# schematic.net
KiCad netlist of a schematic drawn in Altium Designer
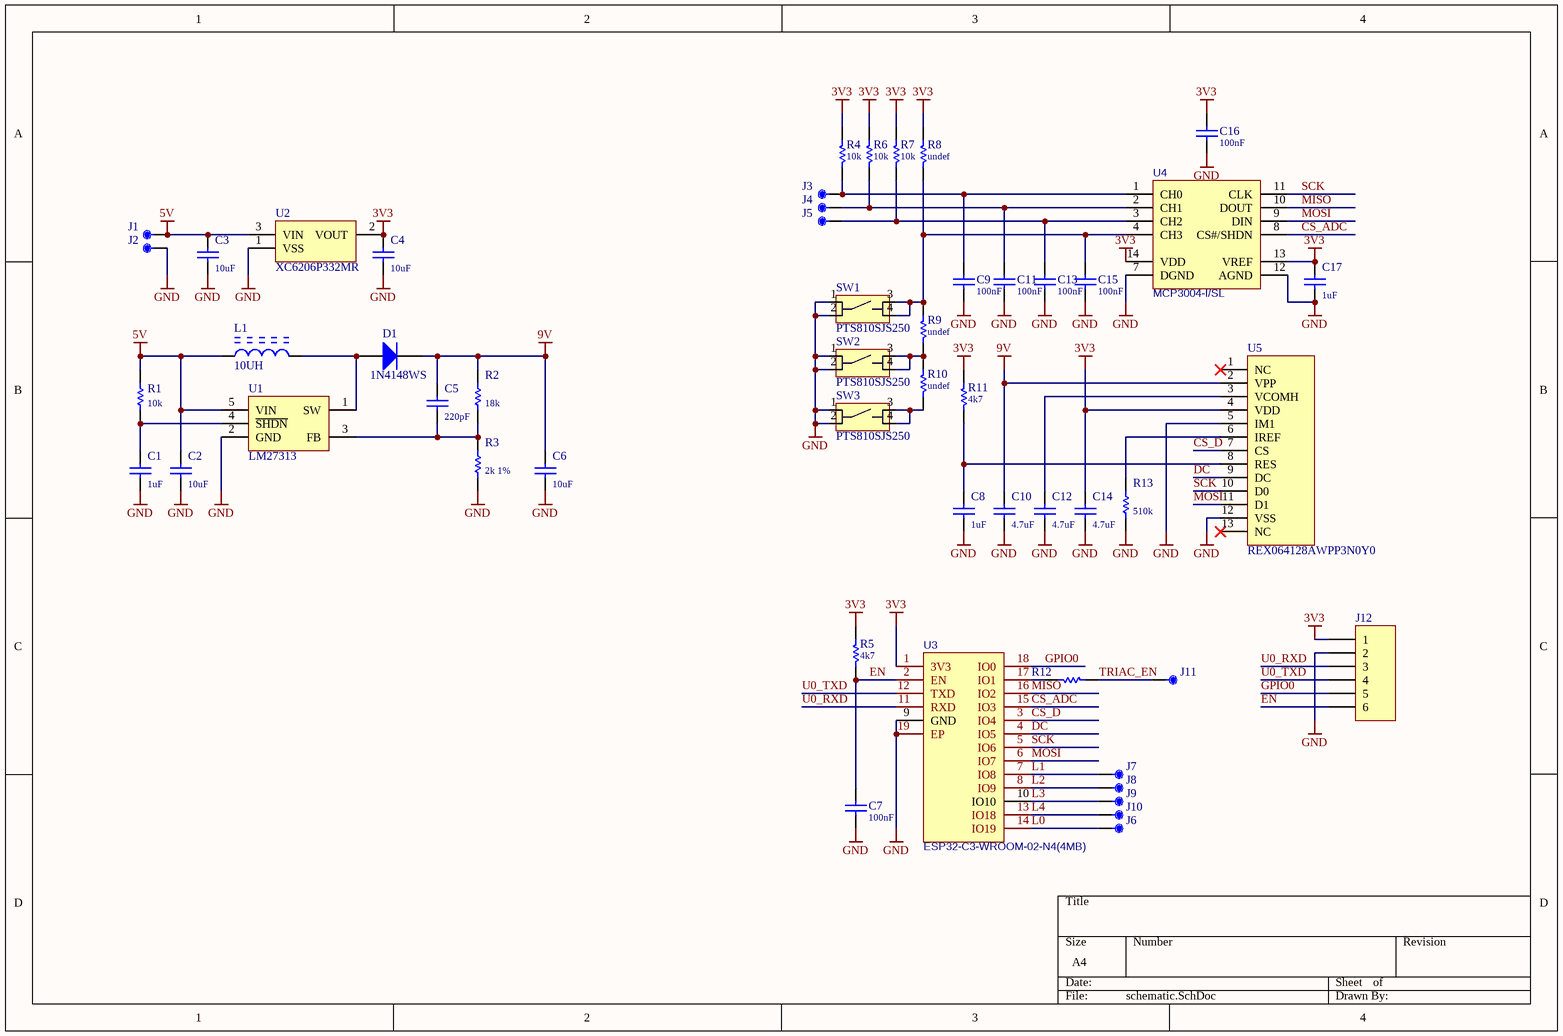
[diagram p0: schematic.SchDoc]

(export (version "E")
  (design (tool "Eeschema 10.0.6"))
  (components
    (comp (ref "C1")
      (value "1uF")
      (footprint "C0603")
      (description "1uF 0603")
      (libsource (lib "Miscellaneous Devices") (part "CAP"))
    )
    (comp (ref "C2")
      (value "10uF")
      (footprint "C1206")
      (description "10uf 25V 1206")
      (libsource (lib "Miscellaneous Devices") (part "CAP"))
    )
    (comp (ref "C3")
      (value "10uF")
      (footprint "C1206")
      (description "10uf 50V 1206")
      (libsource (lib "Miscellaneous Devices") (part "CAP"))
    )
    (comp (ref "C4")
      (value "10uF")
      (footprint "C1206")
      (description "10uf 50V 1206")
      (libsource (lib "Miscellaneous Devices") (part "CAP"))
    )
    (comp (ref "C5")
      (value "220pF")
      (footprint "C0402")
      (description "220pF 0402")
      (libsource (lib "Miscellaneous Devices") (part "CAP"))
    )
    (comp (ref "C6")
      (value "10uF")
      (footprint "C1206")
      (description "10uf 25V 1206")
      (libsource (lib "Miscellaneous Devices") (part "CAP"))
    )
    (comp (ref "C7")
      (value "100nF")
      (footprint "C0402")
      (description "100nF 0402")
      (libsource (lib "Miscellaneous Devices") (part "CAP"))
    )
    (comp (ref "C8")
      (value "1uF")
      (footprint "C0603")
      (description "1uF 0603")
      (libsource (lib "Miscellaneous Devices") (part "CAP"))
    )
    (comp (ref "C9")
      (value "100nF")
      (footprint "C0402")
      (description "100nF 0402")
      (libsource (lib "Miscellaneous Devices") (part "CAP"))
    )
    (comp (ref "C10")
      (value "4.7uF")
      (footprint "C0805")
      (description "4.7uF 50V 0805")
      (libsource (lib "Miscellaneous Devices") (part "CAP"))
    )
    (comp (ref "C11")
      (value "100nF")
      (footprint "C0402")
      (description "100nF 0402")
      (libsource (lib "Miscellaneous Devices") (part "CAP"))
    )
    (comp (ref "C12")
      (value "4.7uF")
      (footprint "C0805")
      (description "4.7uF 50V 0805")
      (libsource (lib "Miscellaneous Devices") (part "CAP"))
    )
    (comp (ref "C13")
      (value "100nF")
      (footprint "C0402")
      (description "100nF 0402")
      (libsource (lib "Miscellaneous Devices") (part "CAP"))
    )
    (comp (ref "C14")
      (value "4.7uF")
      (footprint "C0805")
      (description "4.7uF 50V 0805")
      (libsource (lib "Miscellaneous Devices") (part "CAP"))
    )
    (comp (ref "C15")
      (value "100nF")
      (footprint "C0402")
      (description "100nF 0402")
      (libsource (lib "Miscellaneous Devices") (part "CAP"))
    )
    (comp (ref "C16")
      (value "100nF")
      (footprint "C0402")
      (description "100nF 0402")
      (libsource (lib "Miscellaneous Devices") (part "CAP"))
    )
    (comp (ref "C17")
      (value "1uF")
      (footprint "C0603")
      (description "1uF 0603")
      (libsource (lib "Miscellaneous Devices") (part "CAP"))
    )
    (comp (ref "D1")
      (value "1N4148WS")
      (footprint "SOD-323")
      (libsource (lib "Miscellaneous Devices") (part "US1M-13-F"))
    )
    (comp (ref "J1")
      (value "undef")
      (footprint "TP30_SMD")
      (libsource (lib "Miscellaneous Connectors") (part "TP_Dup1"))
    )
    (comp (ref "J2")
      (value "undef")
      (footprint "TP30_SMD")
      (libsource (lib "Miscellaneous Connectors") (part "TP_Dup1"))
    )
    (comp (ref "J3")
      (value "undef")
      (footprint "TP30_SMD")
      (libsource (lib "Miscellaneous Connectors") (part "TP_Dup1"))
    )
    (comp (ref "J4")
      (value "undef")
      (footprint "TP30_SMD")
      (libsource (lib "Miscellaneous Connectors") (part "TP_Dup1"))
    )
    (comp (ref "J5")
      (value "undef")
      (footprint "TP30_SMD")
      (libsource (lib "Miscellaneous Connectors") (part "TP_Dup1"))
    )
    (comp (ref "J6")
      (value "undef")
      (footprint "TP30_SMD")
      (libsource (lib "Miscellaneous Connectors") (part "TP_Dup1"))
    )
    (comp (ref "J7")
      (value "undef")
      (footprint "TP30_SMD")
      (libsource (lib "Miscellaneous Connectors") (part "TP_Dup1"))
    )
    (comp (ref "J8")
      (value "undef")
      (footprint "TP30_SMD")
      (libsource (lib "Miscellaneous Connectors") (part "TP_Dup1"))
    )
    (comp (ref "J9")
      (value "undef")
      (footprint "TP30_SMD")
      (libsource (lib "Miscellaneous Connectors") (part "TP_Dup1"))
    )
    (comp (ref "J10")
      (value "undef")
      (footprint "TP30_SMD")
      (libsource (lib "Miscellaneous Connectors") (part "TP_Dup1"))
    )
    (comp (ref "J11")
      (value "undef")
      (footprint "TP30_SMD")
      (libsource (lib "Miscellaneous Connectors") (part "TP_Dup1"))
    )
    (comp (ref "J12") (value "~") (footprint "HDR-1X6") (libsource (lib "Schlib1") (part "Header 3_1")))
    (comp (ref "L1")
      (value "10UH")
      (footprint "L2520")
      (description "VLS252012HBX-100M-1")
      (libsource (lib "Miscellaneous Devices") (part "SRN3015-100M"))
    )
    (comp (ref "R1")
      (value "10k")
      (footprint "R0402")
      (description "10k 0402")
      (libsource (lib "Miscellaneous Devices") (part "RES"))
    )
    (comp (ref "R2")
      (value "18k")
      (footprint "R0402")
      (description "18k 0402")
      (libsource (lib "Miscellaneous Devices") (part "RES"))
    )
    (comp (ref "R3")
      (value "2k 1%")
      (footprint "R0402")
      (description "2k 0402")
      (libsource (lib "Miscellaneous Devices") (part "RES"))
    )
    (comp (ref "R4")
      (value "10k")
      (footprint "R0603")
      (description "10k 0603")
      (libsource (lib "Miscellaneous Devices") (part "RES"))
    )
    (comp (ref "R5")
      (value "4k7")
      (footprint "R0603")
      (description "4k7 0603")
      (libsource (lib "Miscellaneous Devices") (part "RES"))
    )
    (comp (ref "R6")
      (value "10k")
      (footprint "R0603")
      (description "10k 0603")
      (libsource (lib "Miscellaneous Devices") (part "RES"))
    )
    (comp (ref "R7")
      (value "10k")
      (footprint "R0603")
      (description "10k 0603")
      (libsource (lib "Miscellaneous Devices") (part "RES"))
    )
    (comp (ref "R8")
      (value "undef")
      (footprint "R0603")
      (libsource (lib "Miscellaneous Devices") (part "RES"))
    )
    (comp (ref "R9")
      (value "undef")
      (footprint "R0603")
      (libsource (lib "Miscellaneous Devices") (part "RES"))
    )
    (comp (ref "R10")
      (value "undef")
      (footprint "R0603")
      (libsource (lib "Miscellaneous Devices") (part "RES"))
    )
    (comp (ref "R11")
      (value "4k7")
      (footprint "R0603")
      (description "4k7 0603")
      (libsource (lib "Miscellaneous Devices") (part "RES"))
    )
    (comp (ref "R12")
      (value "undef")
      (footprint "R0603")
      (libsource (lib "Miscellaneous Devices") (part "RES"))
    )
    (comp (ref "R13")
      (value "510k")
      (footprint "R0603")
      (description "510k 0603")
      (libsource (lib "Miscellaneous Devices") (part "RES"))
    )
    (comp (ref "SW1")
      (value "PTS810SJS250")
      (footprint "BTN_PTS810")
      (libsource (lib "Miscellaneous Devices") (part "Component_1"))
    )
    (comp (ref "SW2")
      (value "PTS810SJS250")
      (footprint "BTN_PTS810")
      (libsource (lib "Miscellaneous Devices") (part "Component_1"))
    )
    (comp (ref "SW3")
      (value "PTS810SJS250")
      (footprint "BTN_PTS810")
      (libsource (lib "Miscellaneous Devices") (part "Component_1"))
    )
    (comp (ref "U1")
      (value "LM27313")
      (footprint "SOT-23-5")
      (description "LM27313XMFX/NOPB")
      (libsource (lib "Miscellaneous Devices") (part "LM27313XMFX"))
    )
    (comp (ref "U2")
      (value "XC6206P332MR")
      (footprint "SOT-23")
      (libsource (lib "Schlib1") (part "Component_4_1"))
    )
    (comp (ref "U3")
      (value "ESP32-C3-WROOM-02-N4(4MB)")
      (footprint "ESP32-C3-WROOM-02-N4-4MB")
      (libsource (lib "Schlib1") (part "ESP32-C3-WROOM-02-N4(4MB)"))
    )
    (comp (ref "U4")
      (value "MCP3004-I/SL")
      (footprint "SOIC-14")
      (libsource (lib "Schlib1") (part "MCP3004-I/SL"))
    )
    (comp (ref "U5")
      (value "REX064128AWPP3N0Y0")
      (footprint "REX064128AWPP3N0Y0")
      (libsource (lib "Schlib1") (part "Header 3"))
    )
  )
  (nets
    (net (code "1") (name "/CS_ADC") (class "Default")
      (node (ref "U3") (pin "15") (pinfunction "IO3_15") (pintype "passive"))
      (node (ref "U4") (pin "8") (pinfunction "CS#/SHDN_8") (pintype "passive"))
    )
    (net (code "2") (name "/CS_D") (class "Default")
      (node (ref "U3") (pin "3") (pinfunction "IO4_3") (pintype "passive"))
      (node (ref "U5") (pin "7") (pinfunction "CS_7") (pintype "passive"))
    )
    (net (code "3") (name "/DC") (class "Default")
      (node (ref "U3") (pin "4") (pinfunction "IO5_4") (pintype "passive"))
      (node (ref "U5") (pin "9") (pinfunction "DC_9") (pintype "passive"))
    )
    (net (code "4") (name "/EN") (class "Default")
      (node (ref "C7") (pin "2") (pinfunction "2_2") (pintype "passive"))
      (node (ref "J12") (pin "6") (pinfunction "6_6") (pintype "passive"))
      (node (ref "R5") (pin "1") (pinfunction "1_1") (pintype "passive"))
      (node (ref "U3") (pin "2") (pinfunction "EN_2") (pintype "passive"))
    )
    (net (code "5") (name "/GPIO0") (class "Default")
      (node (ref "J12") (pin "5") (pinfunction "5_5") (pintype "passive"))
      (node (ref "U3") (pin "18") (pinfunction "IO0_18") (pintype "passive"))
    )
    (net (code "6") (name "/L0") (class "Default")
      (node (ref "J6") (pin "1") (pinfunction "1_1") (pintype "passive"))
      (node (ref "U3") (pin "14") (pinfunction "IO19_14") (pintype "passive"))
    )
    (net (code "7") (name "/L1") (class "Default")
      (node (ref "J7") (pin "1") (pinfunction "1_1") (pintype "passive"))
      (node (ref "U3") (pin "7") (pinfunction "IO8_7") (pintype "passive"))
    )
    (net (code "8") (name "/L2") (class "Default")
      (node (ref "J8") (pin "1") (pinfunction "1_1") (pintype "passive"))
      (node (ref "U3") (pin "8") (pinfunction "IO9_8") (pintype "passive"))
    )
    (net (code "9") (name "/L3") (class "Default")
      (node (ref "J9") (pin "1") (pinfunction "1_1") (pintype "passive"))
      (node (ref "U3") (pin "10") (pinfunction "IO10_10") (pintype "passive"))
    )
    (net (code "10") (name "/L4") (class "Default")
      (node (ref "J10") (pin "1") (pinfunction "1_1") (pintype "passive"))
      (node (ref "U3") (pin "13") (pinfunction "IO18_13") (pintype "passive"))
    )
    (net (code "11") (name "/MISO") (class "Default")
      (node (ref "U3") (pin "16") (pinfunction "IO2_16") (pintype "passive"))
      (node (ref "U4") (pin "10") (pinfunction "DOUT_10") (pintype "passive"))
    )
    (net (code "12") (name "/MOSI") (class "Default")
      (node (ref "U3") (pin "6") (pinfunction "IO7_6") (pintype "passive"))
      (node (ref "U4") (pin "9") (pinfunction "DIN_9") (pintype "passive"))
      (node (ref "U5") (pin "11") (pinfunction "D1_11") (pintype "passive"))
    )
    (net (code "13") (name "/SCK") (class "Default")
      (node (ref "U3") (pin "5") (pinfunction "IO6_5") (pintype "passive"))
      (node (ref "U4") (pin "11") (pinfunction "CLK_11") (pintype "passive"))
      (node (ref "U5") (pin "10") (pinfunction "D0_10") (pintype "passive"))
    )
    (net (code "14") (name "/TRIAC_EN") (class "Default")
      (node (ref "J11") (pin "1") (pinfunction "1_1") (pintype "passive"))
      (node (ref "R12") (pin "1") (pinfunction "1_1") (pintype "passive"))
    )
    (net (code "15") (name "/U0_RXD") (class "Default")
      (node (ref "J12") (pin "3") (pinfunction "3_3") (pintype "passive"))
      (node (ref "U3") (pin "11") (pinfunction "RXD_11") (pintype "passive"))
    )
    (net (code "16") (name "/U0_TXD") (class "Default")
      (node (ref "J12") (pin "4") (pinfunction "4_4") (pintype "passive"))
      (node (ref "U3") (pin "12") (pinfunction "TXD_12") (pintype "passive"))
    )
    (net (code "17") (name "3V3") (class "Default")
      (node (ref "C14") (pin "2") (pinfunction "2_2") (pintype "passive"))
      (node (ref "C16") (pin "2") (pinfunction "2_2") (pintype "passive"))
      (node (ref "C17") (pin "2") (pinfunction "2_2") (pintype "passive"))
      (node (ref "C4") (pin "2") (pinfunction "2_2") (pintype "passive"))
      (node (ref "J12") (pin "1") (pinfunction "1_1") (pintype "passive"))
      (node (ref "R11") (pin "2") (pinfunction "2_2") (pintype "passive"))
      (node (ref "R4") (pin "2") (pinfunction "2_2") (pintype "passive"))
      (node (ref "R5") (pin "2") (pinfunction "2_2") (pintype "passive"))
      (node (ref "R6") (pin "2") (pinfunction "2_2") (pintype "passive"))
      (node (ref "R7") (pin "2") (pinfunction "2_2") (pintype "passive"))
      (node (ref "R8") (pin "1") (pinfunction "1_1") (pintype "passive"))
      (node (ref "U2") (pin "2") (pinfunction "VOUT_2") (pintype "passive"))
      (node (ref "U3") (pin "1") (pinfunction "3V3_1") (pintype "passive"))
      (node (ref "U4") (pin "13") (pinfunction "VREF_13") (pintype "passive"))
      (node (ref "U4") (pin "14") (pinfunction "VDD_14") (pintype "passive"))
      (node (ref "U5") (pin "4") (pinfunction "VDD_4") (pintype "passive"))
    )
    (net (code "18") (name "5V") (class "Default")
      (node (ref "C2") (pin "2") (pinfunction "2_2") (pintype "passive"))
      (node (ref "C3") (pin "2") (pinfunction "2_2") (pintype "passive"))
      (node (ref "J1") (pin "1") (pinfunction "1_1") (pintype "passive"))
      (node (ref "L1") (pin "1") (pinfunction "1_1") (pintype "passive"))
      (node (ref "R1") (pin "1") (pinfunction "1_1") (pintype "passive"))
      (node (ref "U1") (pin "5") (pinfunction "VIN_5") (pintype "passive"))
      (node (ref "U2") (pin "3") (pinfunction "VIN_3") (pintype "passive"))
    )
    (net (code "19") (name "9V") (class "Default")
      (node (ref "C10") (pin "2") (pinfunction "2_2") (pintype "passive"))
      (node (ref "C5") (pin "2") (pinfunction "2_2") (pintype "passive"))
      (node (ref "C6") (pin "2") (pinfunction "2_2") (pintype "passive"))
      (node (ref "D1") (pin "2") (pinfunction "K_2") (pintype "passive"))
      (node (ref "R2") (pin "1") (pinfunction "1_1") (pintype "passive"))
      (node (ref "U5") (pin "2") (pinfunction "VPP_2") (pintype "passive"))
    )
    (net (code "20") (name "GND") (class "Default")
      (node (ref "C1") (pin "1") (pinfunction "1_1") (pintype "passive"))
      (node (ref "C10") (pin "1") (pinfunction "1_1") (pintype "passive"))
      (node (ref "C11") (pin "1") (pinfunction "1_1") (pintype "passive"))
      (node (ref "C12") (pin "1") (pinfunction "1_1") (pintype "passive"))
      (node (ref "C13") (pin "1") (pinfunction "1_1") (pintype "passive"))
      (node (ref "C14") (pin "1") (pinfunction "1_1") (pintype "passive"))
      (node (ref "C15") (pin "1") (pinfunction "1_1") (pintype "passive"))
      (node (ref "C16") (pin "1") (pinfunction "1_1") (pintype "passive"))
      (node (ref "C17") (pin "1") (pinfunction "1_1") (pintype "passive"))
      (node (ref "C2") (pin "1") (pinfunction "1_1") (pintype "passive"))
      (node (ref "C3") (pin "1") (pinfunction "1_1") (pintype "passive"))
      (node (ref "C4") (pin "1") (pinfunction "1_1") (pintype "passive"))
      (node (ref "C6") (pin "1") (pinfunction "1_1") (pintype "passive"))
      (node (ref "C7") (pin "1") (pinfunction "1_1") (pintype "passive"))
      (node (ref "C8") (pin "1") (pinfunction "1_1") (pintype "passive"))
      (node (ref "C9") (pin "1") (pinfunction "1_1") (pintype "passive"))
      (node (ref "J12") (pin "2") (pinfunction "2_2") (pintype "passive"))
      (node (ref "J2") (pin "1") (pinfunction "1_1") (pintype "passive"))
      (node (ref "R13") (pin "2") (pinfunction "2_2") (pintype "passive"))
      (node (ref "R3") (pin "2") (pinfunction "2_2") (pintype "passive"))
      (node (ref "SW1") (pin "1") (pinfunction "1_1") (pintype "passive"))
      (node (ref "SW1") (pin "2") (pinfunction "2_2") (pintype "passive"))
      (node (ref "SW2") (pin "1") (pinfunction "1_1") (pintype "passive"))
      (node (ref "SW2") (pin "2") (pinfunction "2_2") (pintype "passive"))
      (node (ref "SW3") (pin "1") (pinfunction "1_1") (pintype "passive"))
      (node (ref "SW3") (pin "2") (pinfunction "2_2") (pintype "passive"))
      (node (ref "U1") (pin "2") (pinfunction "GND_2") (pintype "passive"))
      (node (ref "U2") (pin "1") (pinfunction "VSS_1") (pintype "passive"))
      (node (ref "U3") (pin "19") (pinfunction "EP_19") (pintype "passive"))
      (node (ref "U3") (pin "9") (pinfunction "GND_9") (pintype "passive"))
      (node (ref "U4") (pin "12") (pinfunction "AGND_12") (pintype "passive"))
      (node (ref "U4") (pin "7") (pinfunction "DGND_7") (pintype "passive"))
      (node (ref "U5") (pin "12") (pinfunction "VSS_12") (pintype "passive"))
      (node (ref "U5") (pin "5") (pinfunction "IM1_5") (pintype "passive"))
    )
    (net (code "21") (name "Net-(D1-A)") (class "Default")
      (node (ref "D1") (pin "1") (pinfunction "A_1") (pintype "passive"))
      (node (ref "L1") (pin "2") (pinfunction "2_2") (pintype "passive"))
      (node (ref "U1") (pin "1") (pinfunction "SW_1") (pintype "passive"))
    )
    (net (code "22") (name "Net-(R10-Pad1)") (class "Default")
      (node (ref "R10") (pin "1") (pinfunction "1_1") (pintype "passive"))
      (node (ref "R9") (pin "2") (pinfunction "2_2") (pintype "passive"))
      (node (ref "SW2") (pin "3") (pinfunction "3_3") (pintype "passive"))
      (node (ref "SW2") (pin "4") (pinfunction "4_4") (pintype "passive"))
    )
    (net (code "23") (name "Net-(R10-Pad2)") (class "Default")
      (node (ref "R10") (pin "2") (pinfunction "2_2") (pintype "passive"))
      (node (ref "SW3") (pin "3") (pinfunction "3_3") (pintype "passive"))
      (node (ref "SW3") (pin "4") (pinfunction "4_4") (pintype "passive"))
    )
    (net (code "24") (name "Net-(U1-FB)") (class "Default")
      (node (ref "C5") (pin "1") (pinfunction "1_1") (pintype "passive"))
      (node (ref "R2") (pin "2") (pinfunction "2_2") (pintype "passive"))
      (node (ref "R3") (pin "1") (pinfunction "1_1") (pintype "passive"))
      (node (ref "U1") (pin "3") (pinfunction "FB_3") (pintype "passive"))
    )
    (net (code "25") (name "Net-(U1-~{SHDN})") (class "Default")
      (node (ref "C1") (pin "2") (pinfunction "2_2") (pintype "passive"))
      (node (ref "R1") (pin "2") (pinfunction "2_2") (pintype "passive"))
      (node (ref "U1") (pin "4") (pinfunction "~{SHDN}_4") (pintype "passive"))
    )
    (net (code "26") (name "Net-(U3-IO1)") (class "Default")
      (node (ref "R12") (pin "2") (pinfunction "2_2") (pintype "passive"))
      (node (ref "U3") (pin "17") (pinfunction "IO1_17") (pintype "passive"))
    )
    (net (code "27") (name "Net-(U4-CH0)") (class "Default")
      (node (ref "C9") (pin "2") (pinfunction "2_2") (pintype "passive"))
      (node (ref "J3") (pin "1") (pinfunction "1_1") (pintype "passive"))
      (node (ref "R4") (pin "1") (pinfunction "1_1") (pintype "passive"))
      (node (ref "U4") (pin "1") (pinfunction "CH0_1") (pintype "passive"))
    )
    (net (code "28") (name "Net-(U4-CH1)") (class "Default")
      (node (ref "C11") (pin "2") (pinfunction "2_2") (pintype "passive"))
      (node (ref "J4") (pin "1") (pinfunction "1_1") (pintype "passive"))
      (node (ref "R6") (pin "1") (pinfunction "1_1") (pintype "passive"))
      (node (ref "U4") (pin "2") (pinfunction "CH1_2") (pintype "passive"))
    )
    (net (code "29") (name "Net-(U4-CH2)") (class "Default")
      (node (ref "C13") (pin "2") (pinfunction "2_2") (pintype "passive"))
      (node (ref "J5") (pin "1") (pinfunction "1_1") (pintype "passive"))
      (node (ref "R7") (pin "1") (pinfunction "1_1") (pintype "passive"))
      (node (ref "U4") (pin "3") (pinfunction "CH2_3") (pintype "passive"))
    )
    (net (code "30") (name "Net-(U4-CH3)") (class "Default")
      (node (ref "C15") (pin "2") (pinfunction "2_2") (pintype "passive"))
      (node (ref "R8") (pin "2") (pinfunction "2_2") (pintype "passive"))
      (node (ref "R9") (pin "1") (pinfunction "1_1") (pintype "passive"))
      (node (ref "SW1") (pin "3") (pinfunction "3_3") (pintype "passive"))
      (node (ref "SW1") (pin "4") (pinfunction "4_4") (pintype "passive"))
      (node (ref "U4") (pin "4") (pinfunction "CH3_4") (pintype "passive"))
    )
    (net (code "31") (name "Net-(U5-IREF)") (class "Default")
      (node (ref "R13") (pin "1") (pinfunction "1_1") (pintype "passive"))
      (node (ref "U5") (pin "6") (pinfunction "IREF_6") (pintype "passive"))
    )
    (net (code "32") (name "Net-(U5-RES)") (class "Default")
      (node (ref "C8") (pin "2") (pinfunction "2_2") (pintype "passive"))
      (node (ref "R11") (pin "1") (pinfunction "1_1") (pintype "passive"))
      (node (ref "U5") (pin "8") (pinfunction "RES_8") (pintype "passive"))
    )
    (net (code "33") (name "Net-(U5-VCOMH)") (class "Default")
      (node (ref "C12") (pin "2") (pinfunction "2_2") (pintype "passive"))
      (node (ref "U5") (pin "3") (pinfunction "VCOMH_3") (pintype "passive"))
    )
    (net (code "34") (name "unconnected-(U5-NC-Pad1)") (class "Default")
      (node (ref "U5") (pin "1") (pinfunction "NC_1") (pintype "passive+no_connect"))
    )
    (net (code "35") (name "unconnected-(U5-NC-Pad13)") (class "Default")
      (node (ref "U5") (pin "13") (pinfunction "NC_13") (pintype "passive+no_connect"))
    )
  )
)
